# GH_Terra_one_side_WRONG.net
KiCad netlist of a schematic drawn in EAGLE
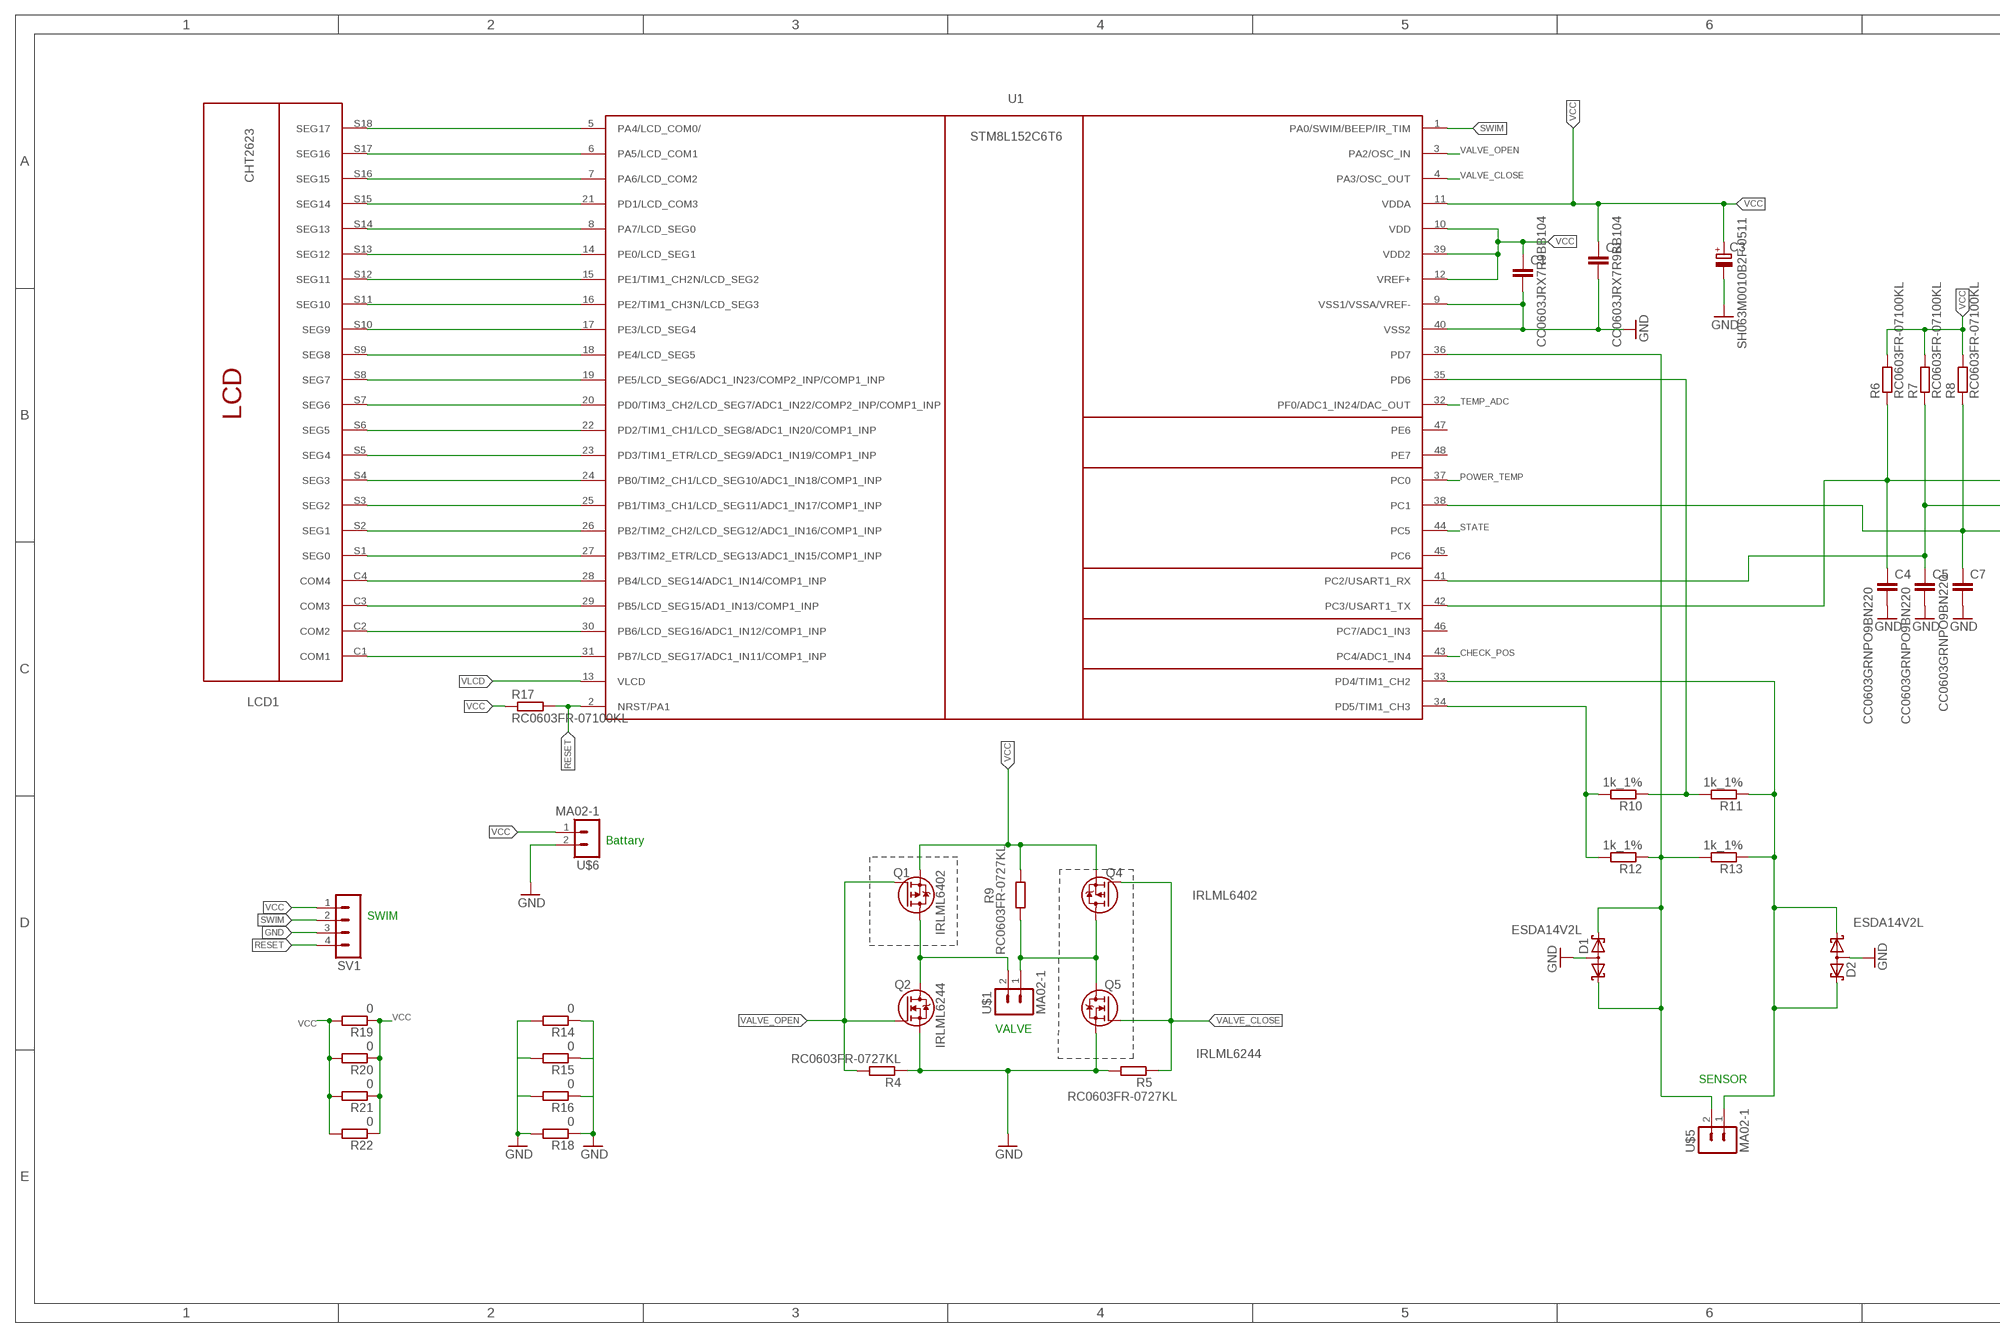
[diagram p0: schematic, sheet 1, part 1 of 2]
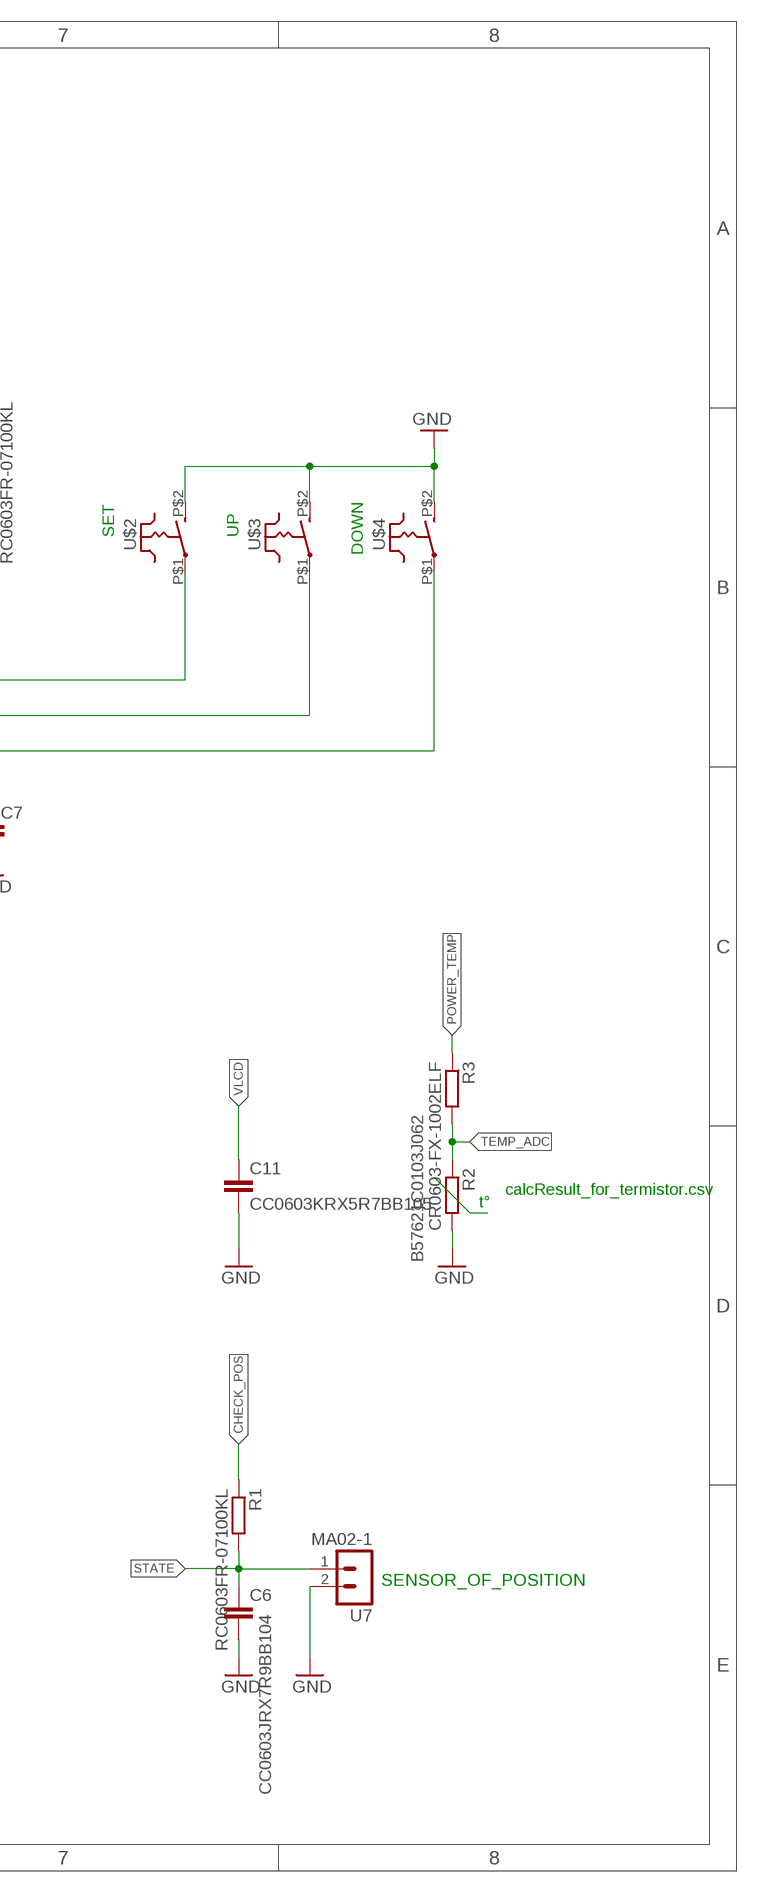
[diagram p1: schematic, sheet 1, part 2 of 2]

(export (version "E")
  (design (tool "Eeschema 10.0.6"))
  (components
    (comp (ref "C1")
      (value "CC0603JRX7R9BB104")
      (footprint "eagle-import:C0603_IPC")
      (libsource (lib "eagle-import") (part "C-EUC0603"))
    )
    (comp (ref "C2")
      (value "CC0603JRX7R9BB104")
      (footprint "eagle-import:C0603_IPC")
      (libsource (lib "eagle-import") (part "C-EUC0603"))
    )
    (comp (ref "C3")
      (value "SH063M0010B2F-0511")
      (footprint "eagle-import:SANYO-OSCON_C6")
      (libsource (lib "eagle-import") (part "CPOL-EUSANYO_C6"))
    )
    (comp (ref "C4")
      (value "CC0603GRNPO9BN220")
      (footprint "eagle-import:C0603_IPC")
      (libsource (lib "eagle-import") (part "C-EUC0603"))
    )
    (comp (ref "C5")
      (value "CC0603GRNPO9BN220")
      (footprint "eagle-import:C0603_IPC")
      (libsource (lib "eagle-import") (part "C-EUC0603"))
    )
    (comp (ref "C6")
      (value "CC0603JRX7R9BB104")
      (footprint "eagle-import:C0603_IPC")
      (libsource (lib "eagle-import") (part "C-EUC0603"))
    )
    (comp (ref "C7")
      (value "CC0603GRNPO9BN220")
      (footprint "eagle-import:C0603_IPC")
      (libsource (lib "eagle-import") (part "C-EUC0603"))
    )
    (comp (ref "C11")
      (value "CC0603KRX5R7BB105")
      (footprint "eagle-import:C0603_IPC")
      (libsource (lib "eagle-import") (part "C-EUC0603"))
    )
    (comp (ref "D1")
      (value "ESDA14V2L")
      (footprint "eagle-import:SOT23")
      (libsource (lib "eagle-import") (part "BAS40-06"))
    )
    (comp (ref "D2")
      (value "ESDA14V2L")
      (footprint "eagle-import:SOT23")
      (libsource (lib "eagle-import") (part "BAS40-06"))
    )
    (comp (ref "LCD1")
      (value "CHT2623")
      (footprint "eagle-import:CHT2623")
      (libsource (lib "eagle-import") (part "CHT2623"))
    )
    (comp (ref "Q1")
      (value "IRLML6402")
      (footprint "eagle-import:SOT23")
      (libsource (lib "eagle-import") (part "PFET-SOT23"))
    )
    (comp (ref "Q2")
      (value "IRLML6244")
      (footprint "eagle-import:SOT23")
      (libsource (lib "eagle-import") (part "NFET-SOT23"))
    )
    (comp (ref "Q4")
      (value "IRLML6402")
      (footprint "eagle-import:SOT23")
      (libsource (lib "eagle-import") (part "PFET-SOT23"))
    )
    (comp (ref "Q5")
      (value "IRLML6244")
      (footprint "eagle-import:SOT23")
      (libsource (lib "eagle-import") (part "NFET-SOT23"))
    )
    (comp (ref "R1")
      (value "RC0603FR-07100KL")
      (footprint "eagle-import:R0603_IPC")
      (libsource (lib "eagle-import") (part "R-EU_R0603"))
    )
    (comp (ref "R2")
      (value "B57621C0103J062")
      (footprint "eagle-import:R1206")
      (libsource (lib "eagle-import") (part "R-EU_R1206"))
    )
    (comp (ref "R3")
      (value "CR0603-FX-1002ELF")
      (footprint "eagle-import:R0603_IPC")
      (libsource (lib "eagle-import") (part "R-EU_R0603"))
    )
    (comp (ref "R4")
      (value "RC0603FR-0727KL")
      (footprint "eagle-import:R0603_IPC")
      (libsource (lib "eagle-import") (part "R-EU_R0603"))
    )
    (comp (ref "R5")
      (value "RC0603FR-0727KL")
      (footprint "eagle-import:R0603_IPC")
      (libsource (lib "eagle-import") (part "R-EU_R0603"))
    )
    (comp (ref "R6")
      (value "RC0603FR-07100KL")
      (footprint "eagle-import:R0603_IPC")
      (libsource (lib "eagle-import") (part "R-EU_R0603"))
    )
    (comp (ref "R7")
      (value "RC0603FR-07100KL")
      (footprint "eagle-import:R0603_IPC")
      (libsource (lib "eagle-import") (part "R-EU_R0603"))
    )
    (comp (ref "R8")
      (value "RC0603FR-07100KL")
      (footprint "eagle-import:R0603_IPC")
      (libsource (lib "eagle-import") (part "R-EU_R0603"))
    )
    (comp (ref "R9")
      (value "RC0603FR-0727KL")
      (footprint "eagle-import:R0603_IPC")
      (libsource (lib "eagle-import") (part "R-EU_R0603"))
    )
    (comp (ref "R10")
      (value "1k_1%")
      (footprint "eagle-import:R0603_IPC")
      (libsource (lib "eagle-import") (part "R-EU_R0603"))
    )
    (comp (ref "R11")
      (value "1k_1%")
      (footprint "eagle-import:R0603_IPC")
      (libsource (lib "eagle-import") (part "R-EU_R0603"))
    )
    (comp (ref "R12")
      (value "1k_1%")
      (footprint "eagle-import:R0603_IPC")
      (libsource (lib "eagle-import") (part "R-EU_R0603"))
    )
    (comp (ref "R13")
      (value "1k_1%")
      (footprint "eagle-import:R0603_IPC")
      (libsource (lib "eagle-import") (part "R-EU_R0603"))
    )
    (comp (ref "R14")
      (value "0")
      (footprint "eagle-import:R0603_IPC")
      (libsource (lib "eagle-import") (part "R-EU_R0603"))
    )
    (comp (ref "R15")
      (value "0")
      (footprint "eagle-import:R0603_IPC")
      (libsource (lib "eagle-import") (part "R-EU_R0603"))
    )
    (comp (ref "R16")
      (value "0")
      (footprint "eagle-import:R0603_IPC")
      (libsource (lib "eagle-import") (part "R-EU_R0603"))
    )
    (comp (ref "R17")
      (value "RC0603FR-07100KL")
      (footprint "eagle-import:R0603_IPC")
      (libsource (lib "eagle-import") (part "R-EU_R0603"))
    )
    (comp (ref "R18")
      (value "0")
      (footprint "eagle-import:R0603_IPC")
      (libsource (lib "eagle-import") (part "R-EU_R0603"))
    )
    (comp (ref "R19")
      (value "0")
      (footprint "eagle-import:R0603_IPC")
      (libsource (lib "eagle-import") (part "R-EU_R0603"))
    )
    (comp (ref "R20")
      (value "0")
      (footprint "eagle-import:R0603_IPC")
      (libsource (lib "eagle-import") (part "R-EU_R0603"))
    )
    (comp (ref "R21")
      (value "0")
      (footprint "eagle-import:R0603_IPC")
      (libsource (lib "eagle-import") (part "R-EU_R0603"))
    )
    (comp (ref "R22")
      (value "0")
      (footprint "eagle-import:R0603_IPC")
      (libsource (lib "eagle-import") (part "R-EU_R0603"))
    )
    (comp (ref "SV1")
      (value "MA04-1")
      (footprint "eagle-import:MA04-1")
      (libsource (lib "eagle-import") (part "MA04-1"))
    )
    (comp (ref "U$1")
      (value "MA02-1")
      (footprint "eagle-import:MA02-1")
      (libsource (lib "eagle-import") (part "MA02-1"))
    )
    (comp (ref "U$2")
      (value "RK_4X3")
      (footprint "eagle-import:RK_3X4")
      (libsource (lib "eagle-import") (part "RK_4X3"))
    )
    (comp (ref "U$3")
      (value "RK_4X3")
      (footprint "eagle-import:RK_3X4")
      (libsource (lib "eagle-import") (part "RK_4X3"))
    )
    (comp (ref "U$4")
      (value "RK_4X3")
      (footprint "eagle-import:RK_3X4")
      (libsource (lib "eagle-import") (part "RK_4X3"))
    )
    (comp (ref "U$5")
      (value "MA02-1")
      (footprint "eagle-import:MA02-1")
      (libsource (lib "eagle-import") (part "MA02-1"))
    )
    (comp (ref "U$6")
      (value "MA02-1")
      (footprint "eagle-import:MA02-1")
      (libsource (lib "eagle-import") (part "MA02-1"))
    )
    (comp (ref "U1")
      (value "STM8L152C6T6")
      (footprint "eagle-import:LQFP48")
      (libsource (lib "eagle-import") (part "STM8L152C6"))
    )
    (comp (ref "U7")
      (value "MA02-1")
      (footprint "eagle-import:MA02-1")
      (libsource (lib "eagle-import") (part "MA02-1"))
    )
  )
  (nets
    (net (code "1") (name "CHECK_POS") (class "Default")
      (node (ref "R1") (pin "1") (pinfunction "1_1") (pintype "passive"))
      (node (ref "U1") (pin "43") (pinfunction "PC4/ADC1_IN4_43") (pintype "bidirectional"))
    )
    (net (code "2") (name "GND") (class "Default")
      (node (ref "C1") (pin "2") (pinfunction "2_2") (pintype "passive"))
      (node (ref "C11") (pin "2") (pinfunction "2_2") (pintype "passive"))
      (node (ref "C2") (pin "2") (pinfunction "2_2") (pintype "passive"))
      (node (ref "C3") (pin "-") (pinfunction "-_-") (pintype "passive"))
      (node (ref "C4") (pin "2") (pinfunction "2_2") (pintype "passive"))
      (node (ref "C5") (pin "2") (pinfunction "2_2") (pintype "passive"))
      (node (ref "C6") (pin "2") (pinfunction "2_2") (pintype "passive"))
      (node (ref "C7") (pin "2") (pinfunction "2_2") (pintype "passive"))
      (node (ref "D1") (pin "3") (pinfunction "AA_3") (pintype "passive"))
      (node (ref "D2") (pin "3") (pinfunction "AA_3") (pintype "passive"))
      (node (ref "Q2") (pin "2") (pinfunction "S_2") (pintype "passive"))
      (node (ref "Q5") (pin "2") (pinfunction "S_2") (pintype "passive"))
      (node (ref "R14") (pin "1") (pinfunction "1_1") (pintype "passive"))
      (node (ref "R14") (pin "2") (pinfunction "2_2") (pintype "passive"))
      (node (ref "R15") (pin "1") (pinfunction "1_1") (pintype "passive"))
      (node (ref "R15") (pin "2") (pinfunction "2_2") (pintype "passive"))
      (node (ref "R16") (pin "1") (pinfunction "1_1") (pintype "passive"))
      (node (ref "R16") (pin "2") (pinfunction "2_2") (pintype "passive"))
      (node (ref "R18") (pin "1") (pinfunction "1_1") (pintype "passive"))
      (node (ref "R18") (pin "2") (pinfunction "2_2") (pintype "passive"))
      (node (ref "R2") (pin "2") (pinfunction "2_2") (pintype "passive"))
      (node (ref "R4") (pin "1") (pinfunction "1_1") (pintype "passive"))
      (node (ref "R5") (pin "2") (pinfunction "2_2") (pintype "passive"))
      (node (ref "SV1") (pin "3") (pinfunction "3_3") (pintype "passive"))
      (node (ref "U$2") (pin "P$2") (pinfunction "S_P$2") (pintype "passive"))
      (node (ref "U$3") (pin "P$2") (pinfunction "S_P$2") (pintype "passive"))
      (node (ref "U$4") (pin "P$2") (pinfunction "S_P$2") (pintype "passive"))
      (node (ref "U$6") (pin "2") (pinfunction "2_2") (pintype "passive"))
      (node (ref "U1") (pin "40") (pinfunction "VSS2_40") (pintype "bidirectional"))
      (node (ref "U1") (pin "9") (pinfunction "VSS1/VSSA/VREF-_9") (pintype "bidirectional"))
      (node (ref "U7") (pin "2") (pinfunction "2_2") (pintype "passive"))
    )
    (net (code "3") (name "Net-(D1-K1)") (class "Default")
      (node (ref "D1") (pin "1") (pinfunction "K1_1") (pintype "passive"))
      (node (ref "D1") (pin "2") (pinfunction "K2_2") (pintype "passive"))
      (node (ref "R12") (pin "1") (pinfunction "1_1") (pintype "passive"))
      (node (ref "R13") (pin "2") (pinfunction "2_2") (pintype "passive"))
      (node (ref "U$5") (pin "2") (pinfunction "2_2") (pintype "passive"))
      (node (ref "U1") (pin "36") (pinfunction "PD7_36") (pintype "bidirectional"))
    )
    (net (code "4") (name "Net-(D2-K1)") (class "Default")
      (node (ref "D2") (pin "1") (pinfunction "K1_1") (pintype "passive"))
      (node (ref "D2") (pin "2") (pinfunction "K2_2") (pintype "passive"))
      (node (ref "R11") (pin "1") (pinfunction "1_1") (pintype "passive"))
      (node (ref "R13") (pin "1") (pinfunction "1_1") (pintype "passive"))
      (node (ref "U$5") (pin "1") (pinfunction "1_1") (pintype "passive"))
      (node (ref "U1") (pin "33") (pinfunction "PD4/TIM1_CH2_33") (pintype "bidirectional"))
    )
    (net (code "5") (name "Net-(LCD1-COM1)") (class "Default")
      (node (ref "LCD1") (pin "C1") (pinfunction "COM1_C1") (pintype "bidirectional"))
      (node (ref "U1") (pin "31") (pinfunction "PB7/LCD_SEG17/ADC1_IN11/COMP1_INP_31") (pintype "bidirectional"))
    )
    (net (code "6") (name "Net-(LCD1-COM2)") (class "Default")
      (node (ref "LCD1") (pin "C2") (pinfunction "COM2_C2") (pintype "bidirectional"))
      (node (ref "U1") (pin "30") (pinfunction "PB6/LCD_SEG16/ADC1_IN12/COMP1_INP_30") (pintype "bidirectional"))
    )
    (net (code "7") (name "Net-(LCD1-COM3)") (class "Default")
      (node (ref "LCD1") (pin "C3") (pinfunction "COM3_C3") (pintype "bidirectional"))
      (node (ref "U1") (pin "29") (pinfunction "PB5/LCD_SEG15/AD1_IN13/COMP1_INP_29") (pintype "bidirectional"))
    )
    (net (code "8") (name "Net-(LCD1-COM4)") (class "Default")
      (node (ref "LCD1") (pin "C4") (pinfunction "COM4_C4") (pintype "bidirectional"))
      (node (ref "U1") (pin "28") (pinfunction "PB4/LCD_SEG14/ADC1_IN14/COMP1_INP_28") (pintype "bidirectional"))
    )
    (net (code "9") (name "Net-(LCD1-SEG0)") (class "Default")
      (node (ref "LCD1") (pin "S1") (pinfunction "SEG0_S1") (pintype "bidirectional"))
      (node (ref "U1") (pin "27") (pinfunction "PB3/TIM2_ETR/LCD_SEG13/ADC1_IN15/COMP1_INP_27") (pintype "bidirectional"))
    )
    (net (code "10") (name "Net-(LCD1-SEG1)") (class "Default")
      (node (ref "LCD1") (pin "S2") (pinfunction "SEG1_S2") (pintype "bidirectional"))
      (node (ref "U1") (pin "26") (pinfunction "PB2/TIM2_CH2/LCD_SEG12/ADC1_IN16/COMP1_INP_26") (pintype "bidirectional"))
    )
    (net (code "11") (name "Net-(LCD1-SEG2)") (class "Default")
      (node (ref "LCD1") (pin "S3") (pinfunction "SEG2_S3") (pintype "bidirectional"))
      (node (ref "U1") (pin "25") (pinfunction "PB1/TIM3_CH1/LCD_SEG11/ADC1_IN17/COMP1_INP_25") (pintype "bidirectional"))
    )
    (net (code "12") (name "Net-(LCD1-SEG3)") (class "Default")
      (node (ref "LCD1") (pin "S4") (pinfunction "SEG3_S4") (pintype "bidirectional"))
      (node (ref "U1") (pin "24") (pinfunction "PB0/TIM2_CH1/LCD_SEG10/ADC1_IN18/COMP1_INP_24") (pintype "bidirectional"))
    )
    (net (code "13") (name "Net-(LCD1-SEG4)") (class "Default")
      (node (ref "LCD1") (pin "S5") (pinfunction "SEG4_S5") (pintype "bidirectional"))
      (node (ref "U1") (pin "23") (pinfunction "PD3/TIM1_ETR/LCD_SEG9/ADC1_IN19/COMP1_INP_23") (pintype "bidirectional"))
    )
    (net (code "14") (name "Net-(LCD1-SEG5)") (class "Default")
      (node (ref "LCD1") (pin "S6") (pinfunction "SEG5_S6") (pintype "bidirectional"))
      (node (ref "U1") (pin "22") (pinfunction "PD2/TIM1_CH1/LCD_SEG8/ADC1_IN20/COMP1_INP_22") (pintype "bidirectional"))
    )
    (net (code "15") (name "Net-(LCD1-SEG6)") (class "Default")
      (node (ref "LCD1") (pin "S7") (pinfunction "SEG6_S7") (pintype "bidirectional"))
      (node (ref "U1") (pin "20") (pinfunction "PD0/TIM3_CH2/LCD_SEG7/ADC1_IN22/COMP2_INP/COMP1_INP_20") (pintype "bidirectional"))
    )
    (net (code "16") (name "Net-(LCD1-SEG7)") (class "Default")
      (node (ref "LCD1") (pin "S8") (pinfunction "SEG7_S8") (pintype "bidirectional"))
      (node (ref "U1") (pin "19") (pinfunction "PE5/LCD_SEG6/ADC1_IN23/COMP2_INP/COMP1_INP_19") (pintype "bidirectional"))
    )
    (net (code "17") (name "Net-(LCD1-SEG8)") (class "Default")
      (node (ref "LCD1") (pin "S9") (pinfunction "SEG8_S9") (pintype "bidirectional"))
      (node (ref "U1") (pin "18") (pinfunction "PE4/LCD_SEG5_18") (pintype "bidirectional"))
    )
    (net (code "18") (name "Net-(LCD1-SEG9)") (class "Default")
      (node (ref "LCD1") (pin "S10") (pinfunction "SEG9_S10") (pintype "bidirectional"))
      (node (ref "U1") (pin "17") (pinfunction "PE3/LCD_SEG4_17") (pintype "bidirectional"))
    )
    (net (code "19") (name "Net-(LCD1-SEG10)") (class "Default")
      (node (ref "LCD1") (pin "S11") (pinfunction "SEG10_S11") (pintype "bidirectional"))
      (node (ref "U1") (pin "16") (pinfunction "PE2/TIM1_CH3N/LCD_SEG3_16") (pintype "bidirectional"))
    )
    (net (code "20") (name "Net-(LCD1-SEG11)") (class "Default")
      (node (ref "LCD1") (pin "S12") (pinfunction "SEG11_S12") (pintype "bidirectional"))
      (node (ref "U1") (pin "15") (pinfunction "PE1/TIM1_CH2N/LCD_SEG2_15") (pintype "bidirectional"))
    )
    (net (code "21") (name "Net-(LCD1-SEG12)") (class "Default")
      (node (ref "LCD1") (pin "S13") (pinfunction "SEG12_S13") (pintype "bidirectional"))
      (node (ref "U1") (pin "14") (pinfunction "PE0/LCD_SEG1_14") (pintype "bidirectional"))
    )
    (net (code "22") (name "Net-(LCD1-SEG13)") (class "Default")
      (node (ref "LCD1") (pin "S14") (pinfunction "SEG13_S14") (pintype "bidirectional"))
      (node (ref "U1") (pin "8") (pinfunction "PA7/LCD_SEG0_8") (pintype "bidirectional"))
    )
    (net (code "23") (name "Net-(LCD1-SEG14)") (class "Default")
      (node (ref "LCD1") (pin "S15") (pinfunction "SEG14_S15") (pintype "bidirectional"))
      (node (ref "U1") (pin "21") (pinfunction "PD1/LCD_COM3_21") (pintype "bidirectional"))
    )
    (net (code "24") (name "Net-(LCD1-SEG15)") (class "Default")
      (node (ref "LCD1") (pin "S16") (pinfunction "SEG15_S16") (pintype "bidirectional"))
      (node (ref "U1") (pin "7") (pinfunction "PA6/LCD_COM2_7") (pintype "bidirectional"))
    )
    (net (code "25") (name "Net-(LCD1-SEG16)") (class "Default")
      (node (ref "LCD1") (pin "S17") (pinfunction "SEG16_S17") (pintype "bidirectional"))
      (node (ref "U1") (pin "6") (pinfunction "PA5/LCD_COM1_6") (pintype "bidirectional"))
    )
    (net (code "26") (name "Net-(LCD1-SEG17)") (class "Default")
      (node (ref "LCD1") (pin "S18") (pinfunction "SEG17_S18") (pintype "bidirectional"))
      (node (ref "U1") (pin "5") (pinfunction "PA4/LCD_COM0/_5") (pintype "bidirectional"))
    )
    (net (code "27") (name "Net-(Q1-D)") (class "Default")
      (node (ref "Q1") (pin "3") (pinfunction "D_3") (pintype "passive"))
      (node (ref "Q2") (pin "3") (pinfunction "D_3") (pintype "passive"))
      (node (ref "U$1") (pin "2") (pinfunction "2_2") (pintype "passive"))
    )
    (net (code "28") (name "Net-(Q4-D)") (class "Default")
      (node (ref "Q4") (pin "3") (pinfunction "D_3") (pintype "passive"))
      (node (ref "Q5") (pin "3") (pinfunction "D_3") (pintype "passive"))
      (node (ref "R9") (pin "2") (pinfunction "2_2") (pintype "passive"))
      (node (ref "U$1") (pin "1") (pinfunction "1_1") (pintype "passive"))
    )
    (net (code "29") (name "Net-(U$2-P)") (class "Default")
      (node (ref "C4") (pin "1") (pinfunction "1_1") (pintype "passive"))
      (node (ref "R6") (pin "1") (pinfunction "1_1") (pintype "passive"))
      (node (ref "U$2") (pin "P$1") (pinfunction "P_P$1") (pintype "passive"))
      (node (ref "U1") (pin "42") (pinfunction "PC3/USART1_TX_42") (pintype "bidirectional"))
    )
    (net (code "30") (name "Net-(U$3-P)") (class "Default")
      (node (ref "C5") (pin "1") (pinfunction "1_1") (pintype "passive"))
      (node (ref "R7") (pin "1") (pinfunction "1_1") (pintype "passive"))
      (node (ref "U$3") (pin "P$1") (pinfunction "P_P$1") (pintype "passive"))
      (node (ref "U1") (pin "41") (pinfunction "PC2/USART1_RX_41") (pintype "bidirectional"))
    )
    (net (code "31") (name "Net-(U$4-P)") (class "Default")
      (node (ref "C7") (pin "1") (pinfunction "1_1") (pintype "passive"))
      (node (ref "R8") (pin "1") (pinfunction "1_1") (pintype "passive"))
      (node (ref "U$4") (pin "P$1") (pinfunction "P_P$1") (pintype "passive"))
      (node (ref "U1") (pin "38") (pinfunction "PC1_38") (pintype "bidirectional"))
    )
    (net (code "32") (name "Net-(U1-PD5{slash}TIM1_CH3)") (class "Default")
      (node (ref "R10") (pin "2") (pinfunction "2_2") (pintype "passive"))
      (node (ref "R12") (pin "2") (pinfunction "2_2") (pintype "passive"))
      (node (ref "U1") (pin "34") (pinfunction "PD5/TIM1_CH3_34") (pintype "bidirectional"))
    )
    (net (code "33") (name "Net-(U1-PD6)") (class "Default")
      (node (ref "R10") (pin "1") (pinfunction "1_1") (pintype "passive"))
      (node (ref "R11") (pin "2") (pinfunction "2_2") (pintype "passive"))
      (node (ref "U1") (pin "35") (pinfunction "PD6_35") (pintype "bidirectional"))
    )
    (net (code "34") (name "POWER_TEMP") (class "Default")
      (node (ref "R3") (pin "1") (pinfunction "1_1") (pintype "passive"))
      (node (ref "U1") (pin "37") (pinfunction "PC0_37") (pintype "bidirectional"))
    )
    (net (code "35") (name "RESET") (class "Default")
      (node (ref "R17") (pin "2") (pinfunction "2_2") (pintype "passive"))
      (node (ref "SV1") (pin "4") (pinfunction "4_4") (pintype "passive"))
      (node (ref "U1") (pin "2") (pinfunction "NRST/PA1_2") (pintype "bidirectional"))
    )
    (net (code "36") (name "STATE") (class "Default")
      (node (ref "C6") (pin "1") (pinfunction "1_1") (pintype "passive"))
      (node (ref "R1") (pin "2") (pinfunction "2_2") (pintype "passive"))
      (node (ref "U1") (pin "44") (pinfunction "PC5_44") (pintype "bidirectional"))
      (node (ref "U7") (pin "1") (pinfunction "1_1") (pintype "passive"))
    )
    (net (code "37") (name "SWIM") (class "Default")
      (node (ref "SV1") (pin "2") (pinfunction "2_2") (pintype "passive"))
      (node (ref "U1") (pin "1") (pinfunction "PA0/SWIM/BEEP/IR_TIM_1") (pintype "bidirectional"))
    )
    (net (code "38") (name "TEMP_ADC") (class "Default")
      (node (ref "R2") (pin "1") (pinfunction "1_1") (pintype "passive"))
      (node (ref "R3") (pin "2") (pinfunction "2_2") (pintype "passive"))
      (node (ref "U1") (pin "32") (pinfunction "PF0/ADC1_IN24/DAC_OUT_32") (pintype "bidirectional"))
    )
    (net (code "39") (name "VALVE_CLOSE") (class "Default")
      (node (ref "Q4") (pin "1") (pinfunction "G_1") (pintype "passive"))
      (node (ref "Q5") (pin "1") (pinfunction "G_1") (pintype "passive"))
      (node (ref "R5") (pin "1") (pinfunction "1_1") (pintype "passive"))
      (node (ref "U1") (pin "4") (pinfunction "PA3/OSC_OUT_4") (pintype "bidirectional"))
    )
    (net (code "40") (name "VALVE_OPEN") (class "Default")
      (node (ref "Q1") (pin "1") (pinfunction "G_1") (pintype "passive"))
      (node (ref "Q2") (pin "1") (pinfunction "G_1") (pintype "passive"))
      (node (ref "R4") (pin "2") (pinfunction "2_2") (pintype "passive"))
      (node (ref "U1") (pin "3") (pinfunction "PA2/OSC_IN_3") (pintype "bidirectional"))
    )
    (net (code "41") (name "VCC") (class "Default")
      (node (ref "C1") (pin "1") (pinfunction "1_1") (pintype "passive"))
      (node (ref "C2") (pin "1") (pinfunction "1_1") (pintype "passive"))
      (node (ref "C3") (pin "+") (pinfunction "+_+") (pintype "passive"))
      (node (ref "Q1") (pin "2") (pinfunction "S_2") (pintype "passive"))
      (node (ref "Q4") (pin "2") (pinfunction "S_2") (pintype "passive"))
      (node (ref "R17") (pin "1") (pinfunction "1_1") (pintype "passive"))
      (node (ref "R19") (pin "1") (pinfunction "1_1") (pintype "passive"))
      (node (ref "R19") (pin "2") (pinfunction "2_2") (pintype "passive"))
      (node (ref "R20") (pin "1") (pinfunction "1_1") (pintype "passive"))
      (node (ref "R20") (pin "2") (pinfunction "2_2") (pintype "passive"))
      (node (ref "R21") (pin "1") (pinfunction "1_1") (pintype "passive"))
      (node (ref "R21") (pin "2") (pinfunction "2_2") (pintype "passive"))
      (node (ref "R22") (pin "1") (pinfunction "1_1") (pintype "passive"))
      (node (ref "R22") (pin "2") (pinfunction "2_2") (pintype "passive"))
      (node (ref "R6") (pin "2") (pinfunction "2_2") (pintype "passive"))
      (node (ref "R7") (pin "2") (pinfunction "2_2") (pintype "passive"))
      (node (ref "R8") (pin "2") (pinfunction "2_2") (pintype "passive"))
      (node (ref "R9") (pin "1") (pinfunction "1_1") (pintype "passive"))
      (node (ref "SV1") (pin "1") (pinfunction "1_1") (pintype "passive"))
      (node (ref "U$6") (pin "1") (pinfunction "1_1") (pintype "passive"))
      (node (ref "U1") (pin "10") (pinfunction "VDD_10") (pintype "bidirectional"))
      (node (ref "U1") (pin "11") (pinfunction "VDDA_11") (pintype "bidirectional"))
      (node (ref "U1") (pin "12") (pinfunction "VREF+_12") (pintype "bidirectional"))
      (node (ref "U1") (pin "39") (pinfunction "VDD2_39") (pintype "bidirectional"))
    )
    (net (code "42") (name "VLCD") (class "Default")
      (node (ref "C11") (pin "1") (pinfunction "1_1") (pintype "passive"))
      (node (ref "U1") (pin "13") (pinfunction "VLCD_13") (pintype "bidirectional"))
    )
    (net (code "43") (name "unconnected-(U1-PC6-Pad45)") (class "Default")
      (node (ref "U1") (pin "45") (pinfunction "PC6_45") (pintype "bidirectional"))
    )
    (net (code "44") (name "unconnected-(U1-PC7{slash}ADC1_IN3-Pad46)") (class "Default")
      (node (ref "U1") (pin "46") (pinfunction "PC7/ADC1_IN3_46") (pintype "bidirectional"))
    )
    (net (code "45") (name "unconnected-(U1-PE6-Pad47)") (class "Default")
      (node (ref "U1") (pin "47") (pinfunction "PE6_47") (pintype "bidirectional"))
    )
    (net (code "46") (name "unconnected-(U1-PE7-Pad48)") (class "Default")
      (node (ref "U1") (pin "48") (pinfunction "PE7_48") (pintype "bidirectional"))
    )
  )
)
